# nixie-fader_rev3.net
KiCad netlist of a schematic drawn in EAGLE
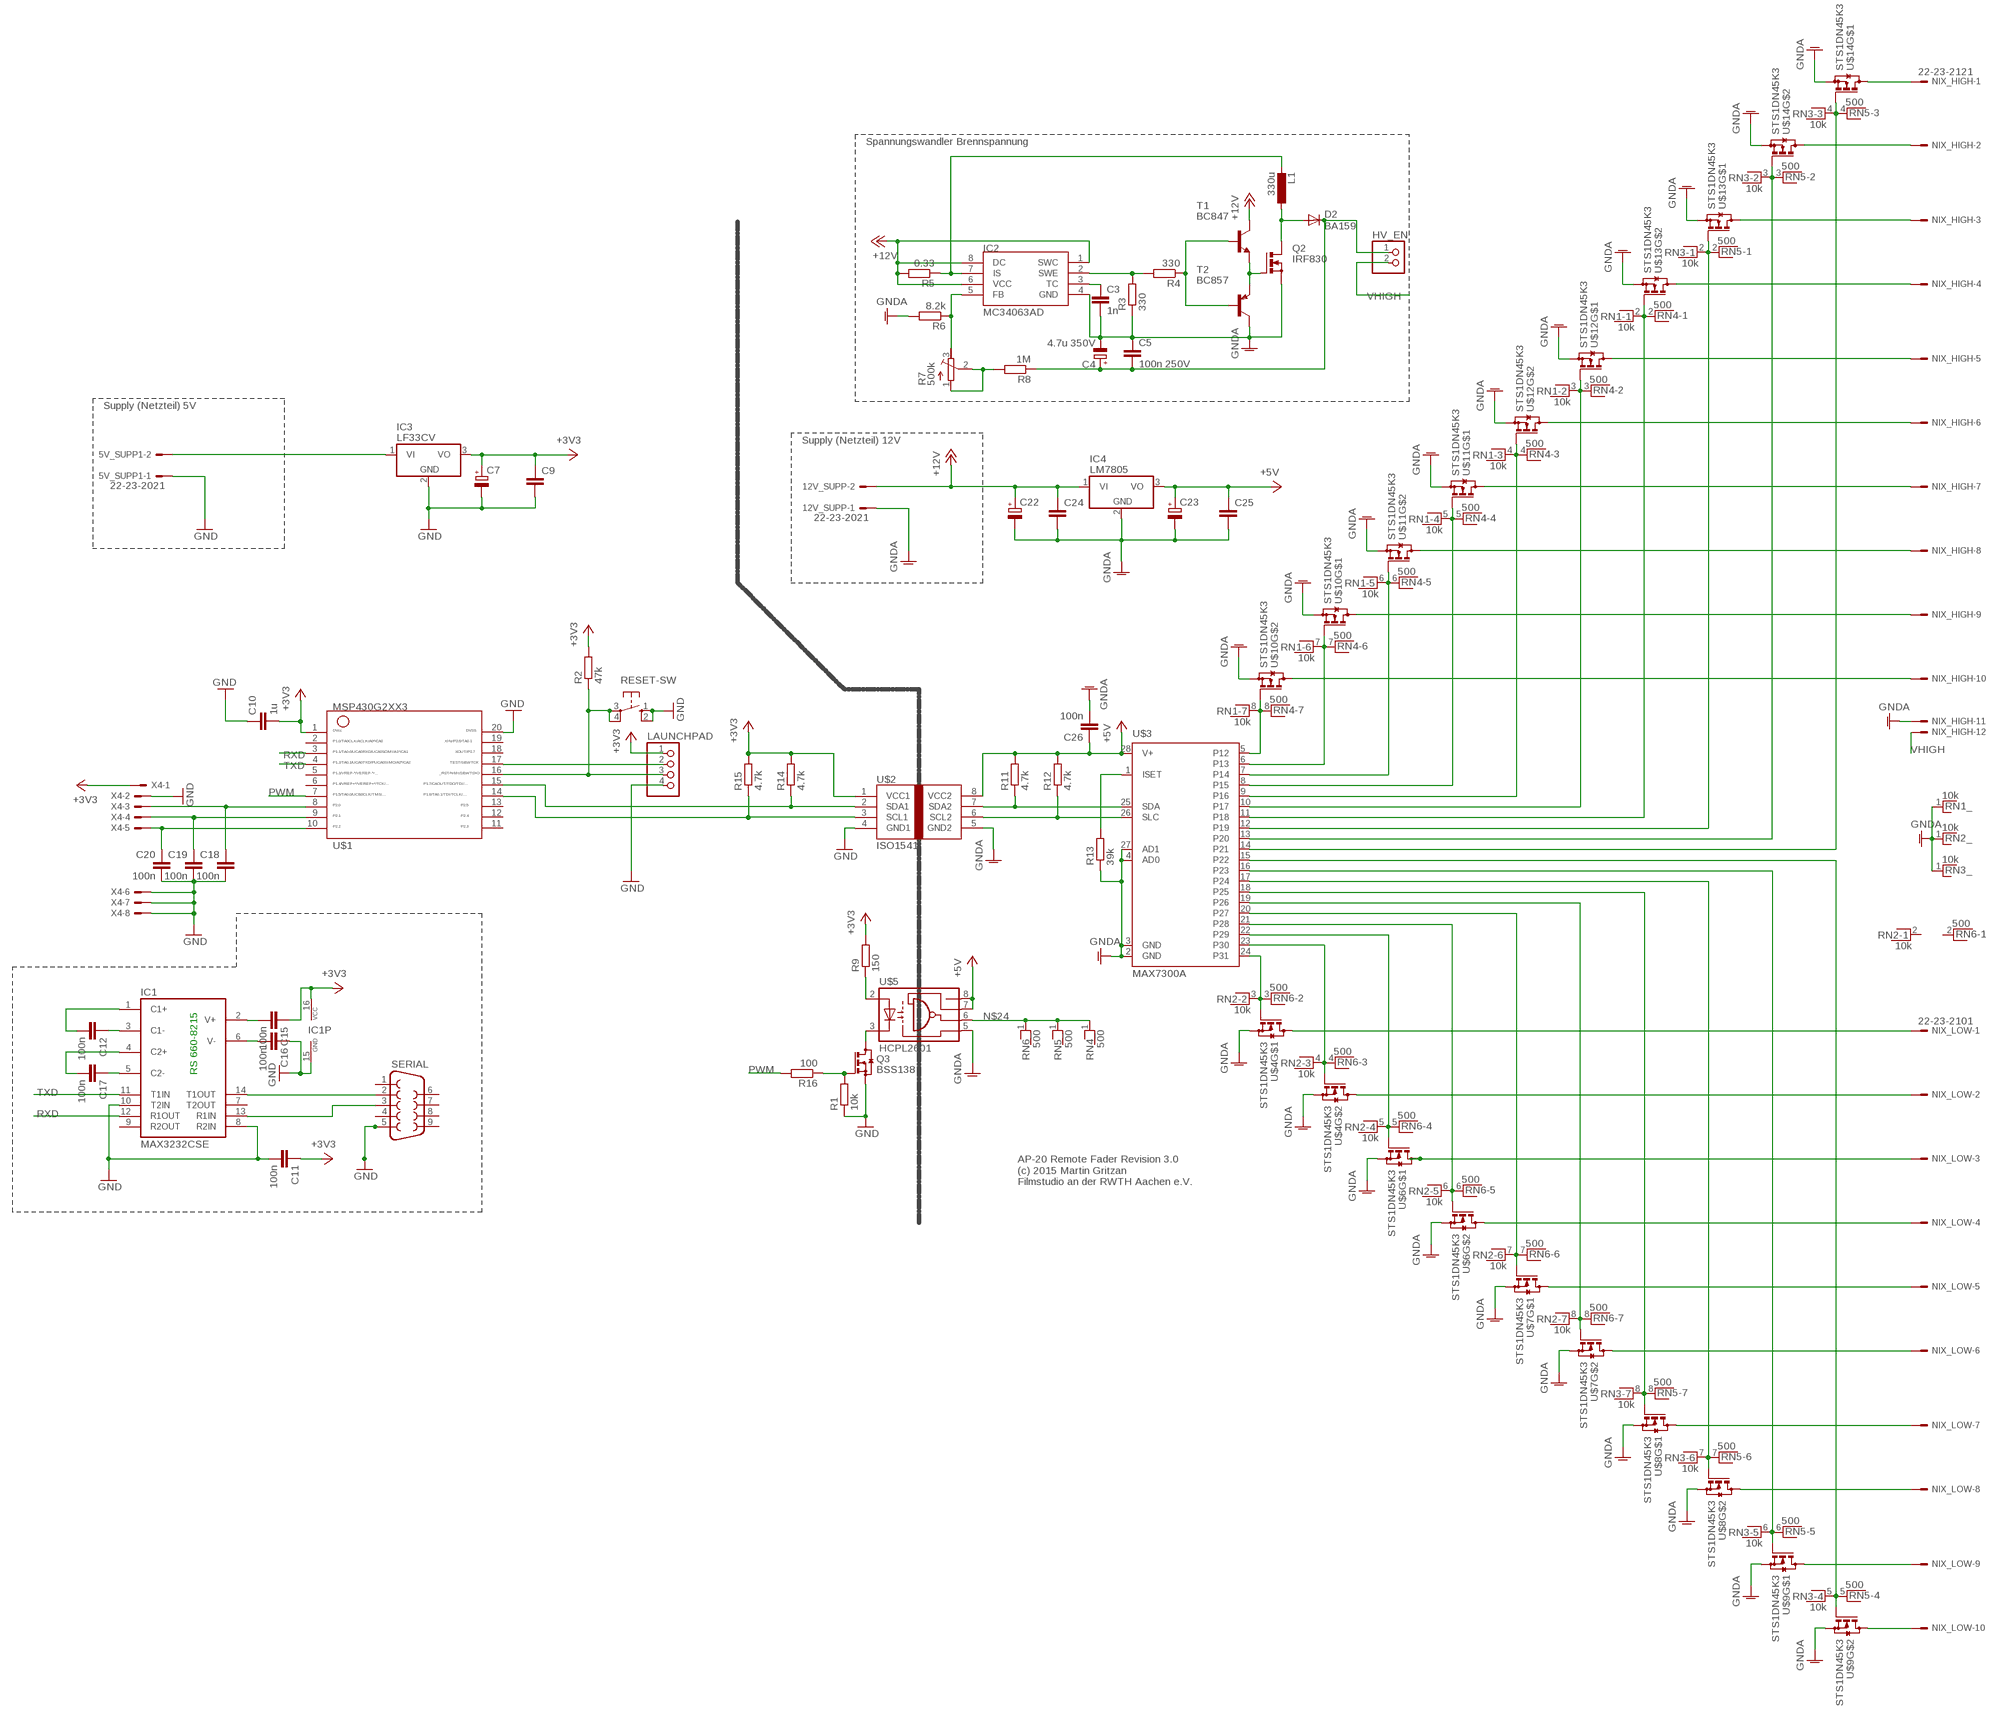
[diagram p0: schematic, sheet 1]

(export (version "E")
  (design (tool "Eeschema 10.0.6"))
  (components
    (comp (ref "5V_SUPP1")
      (value "22-23-2021")
      (footprint "eagle-import:22-23-2021")
      (fields (field (name "MF") "MOLEX"))
      (libsource (lib "eagle-import") (part "22-23-2021"))
    )
    (comp (ref "12V_SUPP")
      (value "22-23-2021")
      (footprint "eagle-import:22-23-2021")
      (fields (field (name "MF") "MOLEX"))
      (libsource (lib "eagle-import") (part "22-23-2021"))
    )
    (comp (ref "C3")
      (value "1n")
      (footprint "eagle-import:C0805")
      (libsource (lib "eagle-import") (part "resistor_C-EUC0805"))
    )
    (comp (ref "C4")
      (value "4.7u 350V")
      (footprint "eagle-import:E5-8,5")
      (libsource (lib "eagle-import") (part "resistor_CPOL-EUE5-8.5"))
    )
    (comp (ref "C5")
      (value "100n 250V")
      (footprint "eagle-import:C050-024X044")
      (libsource (lib "eagle-import") (part "C-EU050-024X044"))
    )
    (comp (ref "C7")
      (value "CPOL-EU140CLH-0810")
      (footprint "eagle-import:140CLH-0810")
      (libsource (lib "eagle-import") (part "CPOL-EU140CLH-0810"))
    )
    (comp (ref "C9")
      (value "C-EUC0805K")
      (footprint "eagle-import:C0805K")
      (libsource (lib "eagle-import") (part "C-EUC0805K"))
    )
    (comp (ref "C10")
      (value "1u")
      (footprint "eagle-import:C0805K")
      (libsource (lib "eagle-import") (part "C-EUC0805K"))
    )
    (comp (ref "C11")
      (value "100n")
      (footprint "eagle-import:C0805")
      (libsource (lib "eagle-import") (part "resistor_C-EUC0805"))
    )
    (comp (ref "C12")
      (value "100n")
      (footprint "eagle-import:C0805")
      (libsource (lib "eagle-import") (part "resistor_C-EUC0805"))
    )
    (comp (ref "C15")
      (value "100n")
      (footprint "eagle-import:C0805")
      (libsource (lib "eagle-import") (part "resistor_C-EUC0805"))
    )
    (comp (ref "C16")
      (value "100n")
      (footprint "eagle-import:C0805")
      (libsource (lib "eagle-import") (part "resistor_C-EUC0805"))
    )
    (comp (ref "C17")
      (value "100n")
      (footprint "eagle-import:C0805")
      (libsource (lib "eagle-import") (part "resistor_C-EUC0805"))
    )
    (comp (ref "C18")
      (value "100n")
      (footprint "eagle-import:C0805")
      (libsource (lib "eagle-import") (part "resistor_C-EUC0805"))
    )
    (comp (ref "C19")
      (value "100n")
      (footprint "eagle-import:C0805")
      (libsource (lib "eagle-import") (part "resistor_C-EUC0805"))
    )
    (comp (ref "C20")
      (value "100n")
      (footprint "eagle-import:C0805")
      (libsource (lib "eagle-import") (part "resistor_C-EUC0805"))
    )
    (comp (ref "C22")
      (value "CPOL-EU140CLH-0810")
      (footprint "eagle-import:140CLH-0810")
      (libsource (lib "eagle-import") (part "CPOL-EU140CLH-0810"))
    )
    (comp (ref "C23")
      (value "CPOL-EU140CLH-0810")
      (footprint "eagle-import:140CLH-0810")
      (libsource (lib "eagle-import") (part "CPOL-EU140CLH-0810"))
    )
    (comp (ref "C24")
      (value "C-EUC0805K")
      (footprint "eagle-import:C0805K")
      (libsource (lib "eagle-import") (part "C-EUC0805K"))
    )
    (comp (ref "C25")
      (value "C-EUC0805K")
      (footprint "eagle-import:C0805K")
      (libsource (lib "eagle-import") (part "C-EUC0805K"))
    )
    (comp (ref "C26")
      (value "100n")
      (footprint "eagle-import:C0805")
      (libsource (lib "eagle-import") (part "resistor_C-EUC0805"))
    )
    (comp (ref "D2")
      (value "BA159")
      (footprint "eagle-import:P1-10")
      (libsource (lib "eagle-import") (part "BA157"))
    )
    (comp (ref "HV_EN")
      (value "PINHD-1X2")
      (footprint "eagle-import:1X02")
      (libsource (lib "eagle-import") (part "PINHD-1X2"))
    )
    (comp (ref "IC1")
      (value "MAX3232CSE")
      (footprint "eagle-import:SO16")
      (libsource (lib "eagle-import") (part "MAX3232SEC"))
    )
    (comp (ref "IC2")
      (value "MC34063AD")
      (footprint "eagle-import:SOIC8")
      (libsource (lib "eagle-import") (part "MC34063AD"))
    )
    (comp (ref "IC3")
      (value "LF33CV")
      (footprint "eagle-import:TO220V")
      (libsource (lib "eagle-import") (part "78TV05"))
    )
    (comp (ref "IC4")
      (value "LM7805")
      (footprint "eagle-import:TO220V")
      (libsource (lib "eagle-import") (part "78TV05"))
    )
    (comp (ref "L1")
      (value "330u")
      (footprint "eagle-import:IRF36")
      (libsource (lib "eagle-import") (part "L-EUIRF-36"))
    )
    (comp (ref "LAUNCHPAD")
      (value "PINHD-1X4")
      (footprint "eagle-import:1X04")
      (libsource (lib "eagle-import") (part "PINHD-1X4"))
    )
    (comp (ref "NIX_HIGH")
      (value "22-23-2121")
      (footprint "eagle-import:22-23-2121")
      (fields (field (name "MF") "MOLEX"))
      (libsource (lib "eagle-import") (part "22-23-2121"))
    )
    (comp (ref "NIX_LOW")
      (value "22-23-2101")
      (footprint "eagle-import:22-23-2101")
      (fields (field (name "MF") "MOLEX"))
      (libsource (lib "eagle-import") (part "22-23-2101"))
    )
    (comp (ref "Q2")
      (value "IRF830")
      (footprint "eagle-import:TO220BV")
      (libsource (lib "eagle-import") (part "IRF512"))
    )
    (comp (ref "Q3")
      (value "BSS138")
      (footprint "eagle-import:SOT23")
      (libsource (lib "eagle-import") (part "BSS123"))
    )
    (comp (ref "R1")
      (value "10k")
      (footprint "eagle-import:M0805")
      (libsource (lib "eagle-import") (part "R-EU_M0805"))
    )
    (comp (ref "R2")
      (value "47k")
      (footprint "eagle-import:R0805")
      (libsource (lib "eagle-import") (part "R-EU_R0805"))
    )
    (comp (ref "R3")
      (value "330")
      (footprint "eagle-import:M0805")
      (libsource (lib "eagle-import") (part "R-EU_M0805"))
    )
    (comp (ref "R4")
      (value "330")
      (footprint "eagle-import:M0805")
      (libsource (lib "eagle-import") (part "R-EU_M0805"))
    )
    (comp (ref "R5")
      (value "0.33")
      (footprint "eagle-import:M0805")
      (libsource (lib "eagle-import") (part "R-EU_M0805"))
    )
    (comp (ref "R6")
      (value "8.2k")
      (footprint "eagle-import:M0805")
      (libsource (lib "eagle-import") (part "R-EU_M0805"))
    )
    (comp (ref "R7")
      (value "500k")
      (footprint "eagle-import:RTRIM3296Y")
      (libsource (lib "eagle-import") (part "R-TRIMM3296Y"))
    )
    (comp (ref "R8")
      (value "1M")
      (footprint "eagle-import:M0805")
      (libsource (lib "eagle-import") (part "R-EU_M0805"))
    )
    (comp (ref "R9")
      (value "150")
      (footprint "eagle-import:M0805")
      (libsource (lib "eagle-import") (part "R-EU_M0805"))
    )
    (comp (ref "R11")
      (value "4.7k")
      (footprint "eagle-import:M0805")
      (libsource (lib "eagle-import") (part "R-EU_M0805"))
    )
    (comp (ref "R12")
      (value "4.7k")
      (footprint "eagle-import:M0805")
      (libsource (lib "eagle-import") (part "R-EU_M0805"))
    )
    (comp (ref "R13")
      (value "39k")
      (footprint "eagle-import:M0805")
      (libsource (lib "eagle-import") (part "R-EU_M0805"))
    )
    (comp (ref "R14")
      (value "4.7k")
      (footprint "eagle-import:M0805")
      (libsource (lib "eagle-import") (part "R-EU_M0805"))
    )
    (comp (ref "R15")
      (value "4.7k")
      (footprint "eagle-import:M0805")
      (libsource (lib "eagle-import") (part "R-EU_M0805"))
    )
    (comp (ref "R16")
      (value "100")
      (footprint "eagle-import:M0805")
      (libsource (lib "eagle-import") (part "R-EU_M0805"))
    )
    (comp (ref "RESET-SW")
      (value "10-XX")
      (footprint "eagle-import:B3F-10XX")
      (fields (field (name "MPN") "B3F-1000"))
      (libsource (lib "eagle-import") (part "10-XX"))
    )
    (comp (ref "RN1")
      (value "10k")
      (footprint "eagle-import:RN-8")
      (libsource (lib "eagle-import") (part "RNX7"))
    )
    (comp (ref "RN2")
      (value "10k")
      (footprint "eagle-import:RN-8")
      (libsource (lib "eagle-import") (part "RNX7"))
    )
    (comp (ref "RN3")
      (value "10k")
      (footprint "eagle-import:RN-8")
      (libsource (lib "eagle-import") (part "RNX7"))
    )
    (comp (ref "RN4")
      (value "500")
      (footprint "eagle-import:RN-8")
      (libsource (lib "eagle-import") (part "RNX7"))
    )
    (comp (ref "RN5")
      (value "500")
      (footprint "eagle-import:RN-8")
      (libsource (lib "eagle-import") (part "RNX7"))
    )
    (comp (ref "RN6")
      (value "500")
      (footprint "eagle-import:RN-8")
      (libsource (lib "eagle-import") (part "RNX7"))
    )
    (comp (ref "SERIAL")
      (value "F09H")
      (footprint "eagle-import:F09H")
      (libsource (lib "eagle-import") (part "F09H"))
    )
    (comp (ref "T1")
      (value "BC847")
      (footprint "eagle-import:SOT23")
      (libsource (lib "eagle-import") (part "BC847"))
    )
    (comp (ref "T2")
      (value "BC857")
      (footprint "eagle-import:SOT23-BEC")
      (libsource (lib "eagle-import") (part "BC857SMDA"))
    )
    (comp (ref "U$1")
      (value "G2XX3---PW20")
      (footprint "eagle-import:PW20")
      (libsource (lib "eagle-import") (part "G2XX3---PW20"))
    )
    (comp (ref "U$2")
      (value "ISO1541")
      (footprint "eagle-import:SOIC8")
      (libsource (lib "eagle-import") (part "ISO1541"))
    )
    (comp (ref "U$3")
      (value "MAX7300A")
      (footprint "eagle-import:SSOP28")
      (libsource (lib "eagle-import") (part "MAX7300A"))
    )
    (comp (ref "U$4")
      (value "STS1DN45K3")
      (footprint "eagle-import:SO08")
      (libsource (lib "eagle-import") (part "STS1DN45K3"))
    )
    (comp (ref "U$5")
      (value "HCPL2601")
      (footprint "eagle-import:DIP8-SMD")
      (libsource (lib "eagle-import") (part "HCPL2601"))
    )
    (comp (ref "U$6")
      (value "STS1DN45K3")
      (footprint "eagle-import:SO08")
      (libsource (lib "eagle-import") (part "STS1DN45K3"))
    )
    (comp (ref "U$7")
      (value "STS1DN45K3")
      (footprint "eagle-import:SO08")
      (libsource (lib "eagle-import") (part "STS1DN45K3"))
    )
    (comp (ref "U$8")
      (value "STS1DN45K3")
      (footprint "eagle-import:SO08")
      (libsource (lib "eagle-import") (part "STS1DN45K3"))
    )
    (comp (ref "U$9")
      (value "STS1DN45K3")
      (footprint "eagle-import:SO08")
      (libsource (lib "eagle-import") (part "STS1DN45K3"))
    )
    (comp (ref "U$10")
      (value "STS1DN45K3")
      (footprint "eagle-import:SO08")
      (libsource (lib "eagle-import") (part "STS1DN45K3"))
    )
    (comp (ref "U$11")
      (value "STS1DN45K3")
      (footprint "eagle-import:SO08")
      (libsource (lib "eagle-import") (part "STS1DN45K3"))
    )
    (comp (ref "U$12")
      (value "STS1DN45K3")
      (footprint "eagle-import:SO08")
      (libsource (lib "eagle-import") (part "STS1DN45K3"))
    )
    (comp (ref "U$13")
      (value "STS1DN45K3")
      (footprint "eagle-import:SO08")
      (libsource (lib "eagle-import") (part "STS1DN45K3"))
    )
    (comp (ref "U$14")
      (value "STS1DN45K3")
      (footprint "eagle-import:SO08")
      (libsource (lib "eagle-import") (part "STS1DN45K3"))
    )
    (comp (ref "X4")
      (value "22-23-2081")
      (footprint "eagle-import:22-23-2081")
      (fields (field (name "MF") "MOLEX"))
      (libsource (lib "eagle-import") (part "22-23-2081"))
    )
  )
  (nets
    (net (code "1") (name "+3V3") (class "Default")
      (node (ref "C10") (pin "2") (pinfunction "2_2") (pintype "passive"))
      (node (ref "C11") (pin "1") (pinfunction "1_1") (pintype "passive"))
      (node (ref "C15") (pin "1") (pinfunction "1_1") (pintype "passive"))
      (node (ref "C7") (pin "+") (pinfunction "+_+") (pintype "passive"))
      (node (ref "C9") (pin "1") (pinfunction "1_1") (pintype "passive"))
      (node (ref "IC1") (pin "16") (pinfunction "VCC_16") (pintype "power_in"))
      (node (ref "IC3") (pin "3") (pinfunction "VO_3") (pintype "passive"))
      (node (ref "LAUNCHPAD") (pin "1") (pinfunction "1_1") (pintype "passive"))
      (node (ref "R14") (pin "2") (pinfunction "2_2") (pintype "passive"))
      (node (ref "R15") (pin "2") (pinfunction "2_2") (pintype "passive"))
      (node (ref "R2") (pin "2") (pinfunction "2_2") (pintype "passive"))
      (node (ref "R9") (pin "2") (pinfunction "2_2") (pintype "passive"))
      (node (ref "U$1") (pin "1") (pinfunction "1_1") (pintype "bidirectional"))
      (node (ref "U$2") (pin "1") (pinfunction "VCC1_1") (pintype "power_in"))
      (node (ref "X4") (pin "1") (pinfunction "S_1") (pintype "passive"))
    )
    (net (code "2") (name "+5V") (class "Default")
      (node (ref "C23") (pin "+") (pinfunction "+_+") (pintype "passive"))
      (node (ref "C25") (pin "1") (pinfunction "1_1") (pintype "passive"))
      (node (ref "C26") (pin "1") (pinfunction "1_1") (pintype "passive"))
      (node (ref "IC4") (pin "3") (pinfunction "VO_3") (pintype "passive"))
      (node (ref "R11") (pin "2") (pinfunction "2_2") (pintype "passive"))
      (node (ref "R12") (pin "2") (pinfunction "2_2") (pintype "passive"))
      (node (ref "U$2") (pin "8") (pinfunction "VCC2_8") (pintype "power_in"))
      (node (ref "U$3") (pin "28") (pinfunction "V+_28") (pintype "power_in"))
      (node (ref "U$5") (pin "7") (pinfunction "EN_7") (pintype "passive"))
      (node (ref "U$5") (pin "8") (pinfunction "VCC_8") (pintype "passive"))
    )
    (net (code "3") (name "+12V") (class "Default")
      (node (ref "12V_SUPP") (pin "2") (pinfunction "S_2") (pintype "passive"))
      (node (ref "C22") (pin "+") (pinfunction "+_+") (pintype "passive"))
      (node (ref "C24") (pin "1") (pinfunction "1_1") (pintype "passive"))
      (node (ref "IC2") (pin "1") (pinfunction "SWC_1") (pintype "passive"))
      (node (ref "IC2") (pin "6") (pinfunction "VCC_6") (pintype "passive"))
      (node (ref "IC2") (pin "8") (pinfunction "DC_8") (pintype "passive"))
      (node (ref "IC4") (pin "1") (pinfunction "VI_1") (pintype "input"))
      (node (ref "R5") (pin "2") (pinfunction "2_2") (pintype "passive"))
      (node (ref "T1") (pin "3") (pinfunction "C_3") (pintype "passive"))
    )
    (net (code "4") (name "/N$24") (class "Default")
      (node (ref "RN4") (pin "1") (pinfunction "1_1") (pintype "passive"))
      (node (ref "RN5") (pin "1") (pinfunction "1_1") (pintype "passive"))
      (node (ref "RN6") (pin "1") (pinfunction "1_1") (pintype "passive"))
      (node (ref "U$5") (pin "6") (pinfunction "OUT_6") (pintype "passive"))
    )
    (net (code "5") (name "/PWM") (class "Default")
      (node (ref "R16") (pin "2") (pinfunction "2_2") (pintype "passive"))
      (node (ref "U$1") (pin "7") (pinfunction "7_7") (pintype "bidirectional"))
    )
    (net (code "6") (name "/RXD") (class "Default")
      (node (ref "IC1") (pin "12") (pinfunction "R1OUT_12") (pintype "output"))
      (node (ref "U$1") (pin "3") (pinfunction "3_3") (pintype "bidirectional"))
    )
    (net (code "7") (name "/TXD") (class "Default")
      (node (ref "IC1") (pin "11") (pinfunction "T1IN_11") (pintype "input"))
      (node (ref "U$1") (pin "4") (pinfunction "4_4") (pintype "bidirectional"))
    )
    (net (code "8") (name "/VHIGH") (class "Default")
      (node (ref "HV_EN") (pin "2") (pinfunction "2_2") (pintype "passive"))
      (node (ref "NIX_HIGH") (pin "12") (pinfunction "S_12") (pintype "passive"))
    )
    (net (code "9") (name "GND") (class "Default")
      (node (ref "5V_SUPP1") (pin "1") (pinfunction "S_1") (pintype "passive"))
      (node (ref "C10") (pin "1") (pinfunction "1_1") (pintype "passive"))
      (node (ref "C11") (pin "2") (pinfunction "2_2") (pintype "passive"))
      (node (ref "C16") (pin "1") (pinfunction "1_1") (pintype "passive"))
      (node (ref "C18") (pin "2") (pinfunction "2_2") (pintype "passive"))
      (node (ref "C19") (pin "2") (pinfunction "2_2") (pintype "passive"))
      (node (ref "C20") (pin "2") (pinfunction "2_2") (pintype "passive"))
      (node (ref "C7") (pin "-") (pinfunction "-_-") (pintype "passive"))
      (node (ref "C9") (pin "2") (pinfunction "2_2") (pintype "passive"))
      (node (ref "IC1") (pin "10") (pinfunction "T2IN_10") (pintype "input"))
      (node (ref "IC1") (pin "15") (pinfunction "GND_15") (pintype "power_in"))
      (node (ref "IC1") (pin "8") (pinfunction "R2IN_8") (pintype "input"))
      (node (ref "IC3") (pin "2") (pinfunction "GND_2") (pintype "passive"))
      (node (ref "LAUNCHPAD") (pin "4") (pinfunction "4_4") (pintype "passive"))
      (node (ref "Q3") (pin "2") (pinfunction "S_2") (pintype "passive"))
      (node (ref "R1") (pin "1") (pinfunction "1_1") (pintype "passive"))
      (node (ref "RESET-SW") (pin "1") (pinfunction "S_1") (pintype "passive"))
      (node (ref "RESET-SW") (pin "2") (pinfunction "S1_2") (pintype "passive"))
      (node (ref "SERIAL") (pin "5") (pinfunction "5_5") (pintype "passive"))
      (node (ref "U$1") (pin "20") (pinfunction "20_20") (pintype "bidirectional"))
      (node (ref "U$2") (pin "4") (pinfunction "GND1_4") (pintype "power_in"))
      (node (ref "X4") (pin "2") (pinfunction "S_2") (pintype "passive"))
      (node (ref "X4") (pin "6") (pinfunction "S_6") (pintype "passive"))
      (node (ref "X4") (pin "7") (pinfunction "S_7") (pintype "passive"))
      (node (ref "X4") (pin "8") (pinfunction "S_8") (pintype "passive"))
    )
    (net (code "10") (name "GNDA") (class "Default")
      (node (ref "12V_SUPP") (pin "1") (pinfunction "S_1") (pintype "passive"))
      (node (ref "C22") (pin "-") (pinfunction "-_-") (pintype "passive"))
      (node (ref "C23") (pin "-") (pinfunction "-_-") (pintype "passive"))
      (node (ref "C24") (pin "2") (pinfunction "2_2") (pintype "passive"))
      (node (ref "C25") (pin "2") (pinfunction "2_2") (pintype "passive"))
      (node (ref "C26") (pin "2") (pinfunction "2_2") (pintype "passive"))
      (node (ref "C3") (pin "2") (pinfunction "2_2") (pintype "passive"))
      (node (ref "C4") (pin "-") (pinfunction "-_-") (pintype "passive"))
      (node (ref "C5") (pin "1") (pinfunction "1_1") (pintype "passive"))
      (node (ref "IC2") (pin "4") (pinfunction "GND_4") (pintype "passive"))
      (node (ref "IC4") (pin "2") (pinfunction "GND_2") (pintype "passive"))
      (node (ref "NIX_HIGH") (pin "11") (pinfunction "S_11") (pintype "passive"))
      (node (ref "Q2") (pin "S") (pinfunction "S_S") (pintype "passive"))
      (node (ref "R13") (pin "1") (pinfunction "1_1") (pintype "passive"))
      (node (ref "R3") (pin "1") (pinfunction "1_1") (pintype "passive"))
      (node (ref "R6") (pin "2") (pinfunction "2_2") (pintype "passive"))
      (node (ref "RN1") (pin "1") (pinfunction "1_1") (pintype "passive"))
      (node (ref "RN2") (pin "1") (pinfunction "1_1") (pintype "passive"))
      (node (ref "RN3") (pin "1") (pinfunction "1_1") (pintype "passive"))
      (node (ref "T2") (pin "C") (pinfunction "C_C") (pintype "passive"))
      (node (ref "U$10") (pin "1") (pinfunction "S_1") (pintype "passive"))
      (node (ref "U$10") (pin "3") (pinfunction "S_3") (pintype "passive"))
      (node (ref "U$11") (pin "1") (pinfunction "S_1") (pintype "passive"))
      (node (ref "U$11") (pin "3") (pinfunction "S_3") (pintype "passive"))
      (node (ref "U$12") (pin "1") (pinfunction "S_1") (pintype "passive"))
      (node (ref "U$12") (pin "3") (pinfunction "S_3") (pintype "passive"))
      (node (ref "U$13") (pin "1") (pinfunction "S_1") (pintype "passive"))
      (node (ref "U$13") (pin "3") (pinfunction "S_3") (pintype "passive"))
      (node (ref "U$14") (pin "1") (pinfunction "S_1") (pintype "passive"))
      (node (ref "U$14") (pin "3") (pinfunction "S_3") (pintype "passive"))
      (node (ref "U$2") (pin "5") (pinfunction "GND2_5") (pintype "power_in"))
      (node (ref "U$3") (pin "2") (pinfunction "GND_2") (pintype "power_in"))
      (node (ref "U$3") (pin "27") (pinfunction "AD1_27") (pintype "input"))
      (node (ref "U$3") (pin "3") (pinfunction "GND_3") (pintype "power_in"))
      (node (ref "U$3") (pin "4") (pinfunction "AD0_4") (pintype "input"))
      (node (ref "U$4") (pin "1") (pinfunction "S_1") (pintype "passive"))
      (node (ref "U$4") (pin "3") (pinfunction "S_3") (pintype "passive"))
      (node (ref "U$5") (pin "5") (pinfunction "GND_5") (pintype "passive"))
      (node (ref "U$6") (pin "1") (pinfunction "S_1") (pintype "passive"))
      (node (ref "U$6") (pin "3") (pinfunction "S_3") (pintype "passive"))
      (node (ref "U$7") (pin "1") (pinfunction "S_1") (pintype "passive"))
      (node (ref "U$7") (pin "3") (pinfunction "S_3") (pintype "passive"))
      (node (ref "U$8") (pin "1") (pinfunction "S_1") (pintype "passive"))
      (node (ref "U$8") (pin "3") (pinfunction "S_3") (pintype "passive"))
      (node (ref "U$9") (pin "1") (pinfunction "S_1") (pintype "passive"))
      (node (ref "U$9") (pin "3") (pinfunction "S_3") (pintype "passive"))
    )
    (net (code "11") (name "Net-(5V_SUPP1B-S)") (class "Default")
      (node (ref "5V_SUPP1") (pin "2") (pinfunction "S_2") (pintype "passive"))
      (node (ref "IC3") (pin "1") (pinfunction "VI_1") (pintype "input"))
    )
    (net (code "12") (name "Net-(C4-Pad+)") (class "Default")
      (node (ref "C4") (pin "+") (pinfunction "+_+") (pintype "passive"))
      (node (ref "C5") (pin "2") (pinfunction "2_2") (pintype "passive"))
      (node (ref "D2") (pin "C") (pinfunction "C_C") (pintype "passive"))
      (node (ref "HV_EN") (pin "1") (pinfunction "1_1") (pintype "passive"))
      (node (ref "R8") (pin "1") (pinfunction "1_1") (pintype "passive"))
    )
    (net (code "13") (name "Net-(D2-PadA)") (class "Default")
      (node (ref "D2") (pin "A") (pinfunction "A_A") (pintype "passive"))
      (node (ref "L1") (pin "1") (pinfunction "1_1") (pintype "passive"))
      (node (ref "Q2") (pin "D") (pinfunction "D_D") (pintype "passive"))
    )
    (net (code "14") (name "Net-(IC1A-C1+)") (class "Default")
      (node (ref "C12") (pin "2") (pinfunction "2_2") (pintype "passive"))
      (node (ref "IC1") (pin "1") (pinfunction "C1+_1") (pintype "bidirectional"))
    )
    (net (code "15") (name "Net-(IC1A-C1-)") (class "Default")
      (node (ref "C12") (pin "1") (pinfunction "1_1") (pintype "passive"))
      (node (ref "IC1") (pin "3") (pinfunction "C1-_3") (pintype "bidirectional"))
    )
    (net (code "16") (name "Net-(IC1A-C2+)") (class "Default")
      (node (ref "C17") (pin "2") (pinfunction "2_2") (pintype "passive"))
      (node (ref "IC1") (pin "4") (pinfunction "C2+_4") (pintype "bidirectional"))
    )
    (net (code "17") (name "Net-(IC1A-C2-)") (class "Default")
      (node (ref "C17") (pin "1") (pinfunction "1_1") (pintype "passive"))
      (node (ref "IC1") (pin "5") (pinfunction "C2-_5") (pintype "bidirectional"))
    )
    (net (code "18") (name "Net-(IC1A-R1IN)") (class "Default")
      (node (ref "IC1") (pin "13") (pinfunction "R1IN_13") (pintype "input"))
      (node (ref "SERIAL") (pin "3") (pinfunction "3_3") (pintype "passive"))
    )
    (net (code "19") (name "Net-(IC1A-T1OUT)") (class "Default")
      (node (ref "IC1") (pin "14") (pinfunction "T1OUT_14") (pintype "output"))
      (node (ref "SERIAL") (pin "2") (pinfunction "2_2") (pintype "passive"))
    )
    (net (code "20") (name "Net-(IC1A-V+)") (class "Default")
      (node (ref "C15") (pin "2") (pinfunction "2_2") (pintype "passive"))
      (node (ref "IC1") (pin "2") (pinfunction "V+_2") (pintype "bidirectional"))
    )
    (net (code "21") (name "Net-(IC1A-V-)") (class "Default")
      (node (ref "C16") (pin "2") (pinfunction "2_2") (pintype "passive"))
      (node (ref "IC1") (pin "6") (pinfunction "V-_6") (pintype "bidirectional"))
    )
    (net (code "22") (name "Net-(IC2-FB)") (class "Default")
      (node (ref "IC2") (pin "5") (pinfunction "FB_5") (pintype "passive"))
      (node (ref "R6") (pin "1") (pinfunction "1_1") (pintype "passive"))
      (node (ref "R7") (pin "3") (pinfunction "A_3") (pintype "passive"))
    )
    (net (code "23") (name "Net-(IC2-IS)") (class "Default")
      (node (ref "IC2") (pin "7") (pinfunction "IS_7") (pintype "passive"))
      (node (ref "L1") (pin "2") (pinfunction "2_2") (pintype "passive"))
      (node (ref "R5") (pin "1") (pinfunction "1_1") (pintype "passive"))
    )
    (net (code "24") (name "Net-(IC2-SWE)") (class "Default")
      (node (ref "IC2") (pin "2") (pinfunction "SWE_2") (pintype "passive"))
      (node (ref "R3") (pin "2") (pinfunction "2_2") (pintype "passive"))
      (node (ref "R4") (pin "2") (pinfunction "2_2") (pintype "passive"))
    )
    (net (code "25") (name "Net-(IC2-TC)") (class "Default")
      (node (ref "C3") (pin "1") (pinfunction "1_1") (pintype "passive"))
      (node (ref "IC2") (pin "3") (pinfunction "TC_3") (pintype "passive"))
    )
    (net (code "26") (name "Net-(LAUNCHPAD-Pad2)") (class "Default")
      (node (ref "LAUNCHPAD") (pin "2") (pinfunction "2_2") (pintype "passive"))
      (node (ref "U$1") (pin "17") (pinfunction "17_17") (pintype "bidirectional"))
    )
    (net (code "27") (name "Net-(NIX_HIGHA-S)") (class "Default")
      (node (ref "NIX_HIGH") (pin "1") (pinfunction "S_1") (pintype "passive"))
      (node (ref "U$14") (pin "7") (pinfunction "D_7") (pintype "passive"))
      (node (ref "U$14") (pin "8") (pinfunction "D_8") (pintype "passive"))
    )
    (net (code "28") (name "Net-(NIX_HIGHB-S)") (class "Default")
      (node (ref "NIX_HIGH") (pin "10") (pinfunction "S_10") (pintype "passive"))
      (node (ref "U$10") (pin "5") (pinfunction "D_5") (pintype "passive"))
      (node (ref "U$10") (pin "6") (pinfunction "D_6") (pintype "passive"))
    )
    (net (code "29") (name "Net-(NIX_HIGHE-S)") (class "Default")
      (node (ref "NIX_HIGH") (pin "2") (pinfunction "S_2") (pintype "passive"))
      (node (ref "U$14") (pin "5") (pinfunction "D_5") (pintype "passive"))
      (node (ref "U$14") (pin "6") (pinfunction "D_6") (pintype "passive"))
    )
    (net (code "30") (name "Net-(NIX_HIGHF-S)") (class "Default")
      (node (ref "NIX_HIGH") (pin "3") (pinfunction "S_3") (pintype "passive"))
      (node (ref "U$13") (pin "7") (pinfunction "D_7") (pintype "passive"))
      (node (ref "U$13") (pin "8") (pinfunction "D_8") (pintype "passive"))
    )
    (net (code "31") (name "Net-(NIX_HIGHG-S)") (class "Default")
      (node (ref "NIX_HIGH") (pin "4") (pinfunction "S_4") (pintype "passive"))
      (node (ref "U$13") (pin "5") (pinfunction "D_5") (pintype "passive"))
      (node (ref "U$13") (pin "6") (pinfunction "D_6") (pintype "passive"))
    )
    (net (code "32") (name "Net-(NIX_HIGHH-S)") (class "Default")
      (node (ref "NIX_HIGH") (pin "5") (pinfunction "S_5") (pintype "passive"))
      (node (ref "U$12") (pin "7") (pinfunction "D_7") (pintype "passive"))
      (node (ref "U$12") (pin "8") (pinfunction "D_8") (pintype "passive"))
    )
    (net (code "33") (name "Net-(NIX_HIGHI-S)") (class "Default")
      (node (ref "NIX_HIGH") (pin "6") (pinfunction "S_6") (pintype "passive"))
      (node (ref "U$12") (pin "5") (pinfunction "D_5") (pintype "passive"))
      (node (ref "U$12") (pin "6") (pinfunction "D_6") (pintype "passive"))
    )
    (net (code "34") (name "Net-(NIX_HIGHJ-S)") (class "Default")
      (node (ref "NIX_HIGH") (pin "7") (pinfunction "S_7") (pintype "passive"))
      (node (ref "U$11") (pin "7") (pinfunction "D_7") (pintype "passive"))
      (node (ref "U$11") (pin "8") (pinfunction "D_8") (pintype "passive"))
    )
    (net (code "35") (name "Net-(NIX_HIGHK-S)") (class "Default")
      (node (ref "NIX_HIGH") (pin "8") (pinfunction "S_8") (pintype "passive"))
      (node (ref "U$11") (pin "5") (pinfunction "D_5") (pintype "passive"))
      (node (ref "U$11") (pin "6") (pinfunction "D_6") (pintype "passive"))
    )
    (net (code "36") (name "Net-(NIX_HIGHL-S)") (class "Default")
      (node (ref "NIX_HIGH") (pin "9") (pinfunction "S_9") (pintype "passive"))
      (node (ref "U$10") (pin "7") (pinfunction "D_7") (pintype "passive"))
      (node (ref "U$10") (pin "8") (pinfunction "D_8") (pintype "passive"))
    )
    (net (code "37") (name "Net-(NIX_LOWA-S)") (class "Default")
      (node (ref "NIX_LOW") (pin "1") (pinfunction "S_1") (pintype "passive"))
      (node (ref "U$4") (pin "7") (pinfunction "D_7") (pintype "passive"))
      (node (ref "U$4") (pin "8") (pinfunction "D_8") (pintype "passive"))
    )
    (net (code "38") (name "Net-(NIX_LOWB-S)") (class "Default")
      (node (ref "NIX_LOW") (pin "10") (pinfunction "S_10") (pintype "passive"))
      (node (ref "U$9") (pin "5") (pinfunction "D_5") (pintype "passive"))
      (node (ref "U$9") (pin "6") (pinfunction "D_6") (pintype "passive"))
    )
    (net (code "39") (name "Net-(NIX_LOWC-S)") (class "Default")
      (node (ref "NIX_LOW") (pin "2") (pinfunction "S_2") (pintype "passive"))
      (node (ref "U$4") (pin "5") (pinfunction "D_5") (pintype "passive"))
      (node (ref "U$4") (pin "6") (pinfunction "D_6") (pintype "passive"))
    )
    (net (code "40") (name "Net-(NIX_LOWD-S)") (class "Default")
      (node (ref "NIX_LOW") (pin "3") (pinfunction "S_3") (pintype "passive"))
      (node (ref "U$6") (pin "7") (pinfunction "D_7") (pintype "passive"))
      (node (ref "U$6") (pin "8") (pinfunction "D_8") (pintype "passive"))
    )
    (net (code "41") (name "Net-(NIX_LOWE-S)") (class "Default")
      (node (ref "NIX_LOW") (pin "4") (pinfunction "S_4") (pintype "passive"))
      (node (ref "U$6") (pin "5") (pinfunction "D_5") (pintype "passive"))
      (node (ref "U$6") (pin "6") (pinfunction "D_6") (pintype "passive"))
    )
    (net (code "42") (name "Net-(NIX_LOWF-S)") (class "Default")
      (node (ref "NIX_LOW") (pin "5") (pinfunction "S_5") (pintype "passive"))
      (node (ref "U$7") (pin "7") (pinfunction "D_7") (pintype "passive"))
      (node (ref "U$7") (pin "8") (pinfunction "D_8") (pintype "passive"))
    )
    (net (code "43") (name "Net-(NIX_LOWG-S)") (class "Default")
      (node (ref "NIX_LOW") (pin "6") (pinfunction "S_6") (pintype "passive"))
      (node (ref "U$7") (pin "5") (pinfunction "D_5") (pintype "passive"))
      (node (ref "U$7") (pin "6") (pinfunction "D_6") (pintype "passive"))
    )
    (net (code "44") (name "Net-(NIX_LOWH-S)") (class "Default")
      (node (ref "NIX_LOW") (pin "7") (pinfunction "S_7") (pintype "passive"))
      (node (ref "U$8") (pin "7") (pinfunction "D_7") (pintype "passive"))
      (node (ref "U$8") (pin "8") (pinfunction "D_8") (pintype "passive"))
    )
    (net (code "45") (name "Net-(NIX_LOWI-S)") (class "Default")
      (node (ref "NIX_LOW") (pin "8") (pinfunction "S_8") (pintype "passive"))
      (node (ref "U$8") (pin "5") (pinfunction "D_5") (pintype "passive"))
      (node (ref "U$8") (pin "6") (pinfunction "D_6") (pintype "passive"))
    )
    (net (code "46") (name "Net-(NIX_LOWJ-S)") (class "Default")
      (node (ref "NIX_LOW") (pin "9") (pinfunction "S_9") (pintype "passive"))
      (node (ref "U$9") (pin "7") (pinfunction "D_7") (pintype "passive"))
      (node (ref "U$9") (pin "8") (pinfunction "D_8") (pintype "passive"))
    )
    (net (code "47") (name "Net-(Q3-D)") (class "Default")
      (node (ref "Q3") (pin "3") (pinfunction "D_3") (pintype "passive"))
      (node (ref "U$5") (pin "3") (pinfunction "C_3") (pintype "passive"))
    )
    (net (code "48") (name "Net-(Q3-G)") (class "Default")
      (node (ref "Q3") (pin "1") (pinfunction "G_1") (pintype "passive"))
      (node (ref "R1") (pin "2") (pinfunction "2_2") (pintype "passive"))
      (node (ref "R16") (pin "1") (pinfunction "1_1") (pintype "passive"))
    )
    (net (code "49") (name "Net-(R7-E)") (class "Default")
      (node (ref "R7") (pin "1") (pinfunction "E_1") (pintype "passive"))
      (node (ref "R7") (pin "2") (pinfunction "S_2") (pintype "passive"))
      (node (ref "R8") (pin "2") (pinfunction "2_2") (pintype "passive"))
    )
    (net (code "50") (name "Net-(RESET-SW-P)") (class "Default")
      (node (ref "LAUNCHPAD") (pin "3") (pinfunction "3_3") (pintype "passive"))
      (node (ref "R2") (pin "1") (pinfunction "1_1") (pintype "passive"))
      (node (ref "RESET-SW") (pin "3") (pinfunction "P_3") (pintype "passive"))
      (node (ref "RESET-SW") (pin "4") (pinfunction "P1_4") (pintype "passive"))
      (node (ref "U$1") (pin "16") (pinfunction "16_16") (pintype "bidirectional"))
    )
    (net (code "51") (name "Net-(RN1A-1)") (class "Default")
      (node (ref "RN1") (pin "2") (pinfunction "1_2") (pintype "passive"))
      (node (ref "RN4") (pin "2") (pinfunction "1_2") (pintype "passive"))
      (node (ref "U$13") (pin "4") (pinfunction "G_4") (pintype "passive"))
      (node (ref "U$3") (pin "11") (pinfunction "P18_11") (pintype "bidirectional"))
    )
    (net (code "52") (name "Net-(RN1B-1)") (class "Default")
      (node (ref "RN1") (pin "3") (pinfunction "1_3") (pintype "passive"))
      (node (ref "RN4") (pin "3") (pinfunction "1_3") (pintype "passive"))
      (node (ref "U$12") (pin "2") (pinfunction "G_2") (pintype "passive"))
      (node (ref "U$3") (pin "10") (pinfunction "P17_10") (pintype "bidirectional"))
    )
    (net (code "53") (name "Net-(RN1C-1)") (class "Default")
      (node (ref "RN1") (pin "4") (pinfunction "1_4") (pintype "passive"))
      (node (ref "RN4") (pin "4") (pinfunction "1_4") (pintype "passive"))
      (node (ref "U$12") (pin "4") (pinfunction "G_4") (pintype "passive"))
      (node (ref "U$3") (pin "9") (pinfunction "P16_9") (pintype "bidirectional"))
    )
    (net (code "54") (name "Net-(RN1D-1)") (class "Default")
      (node (ref "RN1") (pin "5") (pinfunction "1_5") (pintype "passive"))
      (node (ref "RN4") (pin "5") (pinfunction "1_5") (pintype "passive"))
      (node (ref "U$11") (pin "2") (pinfunction "G_2") (pintype "passive"))
      (node (ref "U$3") (pin "8") (pinfunction "P15_8") (pintype "bidirectional"))
    )
    (net (code "55") (name "Net-(RN1E-1)") (class "Default")
      (node (ref "RN1") (pin "6") (pinfunction "1_6") (pintype "passive"))
      (node (ref "RN4") (pin "6") (pinfunction "1_6") (pintype "passive"))
      (node (ref "U$11") (pin "4") (pinfunction "G_4") (pintype "passive"))
      (node (ref "U$3") (pin "7") (pinfunction "P14_7") (pintype "bidirectional"))
    )
    (net (code "56") (name "Net-(RN1F-1)") (class "Default")
      (node (ref "RN1") (pin "7") (pinfunction "1_7") (pintype "passive"))
      (node (ref "RN4") (pin "7") (pinfunction "1_7") (pintype "passive"))
      (node (ref "U$10") (pin "2") (pinfunction "G_2") (pintype "passive"))
      (node (ref "U$3") (pin "6") (pinfunction "P13_6") (pintype "bidirectional"))
    )
    (net (code "57") (name "Net-(RN1G-1)") (class "Default")
      (node (ref "RN1") (pin "8") (pinfunction "1_8") (pintype "passive"))
      (node (ref "RN4") (pin "8") (pinfunction "1_8") (pintype "passive"))
      (node (ref "U$10") (pin "4") (pinfunction "G_4") (pintype "passive"))
      (node (ref "U$3") (pin "5") (pinfunction "P12_5") (pintype "bidirectional"))
    )
    (net (code "58") (name "Net-(RN2B-1)") (class "Default")
      (node (ref "RN2") (pin "3") (pinfunction "1_3") (pintype "passive"))
      (node (ref "RN6") (pin "3") (pinfunction "1_3") (pintype "passive"))
      (node (ref "U$3") (pin "24") (pinfunction "P31_24") (pintype "bidirectional"))
      (node (ref "U$4") (pin "2") (pinfunction "G_2") (pintype "passive"))
    )
    (net (code "59") (name "Net-(RN2C-1)") (class "Default")
      (node (ref "RN2") (pin "4") (pinfunction "1_4") (pintype "passive"))
      (node (ref "RN6") (pin "4") (pinfunction "1_4") (pintype "passive"))
      (node (ref "U$3") (pin "23") (pinfunction "P30_23") (pintype "bidirectional"))
      (node (ref "U$4") (pin "4") (pinfunction "G_4") (pintype "passive"))
    )
    (net (code "60") (name "Net-(RN2D-1)") (class "Default")
      (node (ref "RN2") (pin "5") (pinfunction "1_5") (pintype "passive"))
      (node (ref "RN6") (pin "5") (pinfunction "1_5") (pintype "passive"))
      (node (ref "U$3") (pin "22") (pinfunction "P29_22") (pintype "bidirectional"))
      (node (ref "U$6") (pin "2") (pinfunction "G_2") (pintype "passive"))
    )
    (net (code "61") (name "Net-(RN2E-1)") (class "Default")
      (node (ref "RN2") (pin "6") (pinfunction "1_6") (pintype "passive"))
      (node (ref "RN6") (pin "6") (pinfunction "1_6") (pintype "passive"))
      (node (ref "U$3") (pin "21") (pinfunction "P28_21") (pintype "bidirectional"))
      (node (ref "U$6") (pin "4") (pinfunction "G_4") (pintype "passive"))
    )
    (net (code "62") (name "Net-(RN2F-1)") (class "Default")
      (node (ref "RN2") (pin "7") (pinfunction "1_7") (pintype "passive"))
      (node (ref "RN6") (pin "7") (pinfunction "1_7") (pintype "passive"))
      (node (ref "U$3") (pin "20") (pinfunction "P27_20") (pintype "bidirectional"))
      (node (ref "U$7") (pin "2") (pinfunction "G_2") (pintype "passive"))
    )
    (net (code "63") (name "Net-(RN2G-1)") (class "Default")
      (node (ref "RN2") (pin "8") (pinfunction "1_8") (pintype "passive"))
      (node (ref "RN6") (pin "8") (pinfunction "1_8") (pintype "passive"))
      (node (ref "U$3") (pin "19") (pinfunction "P26_19") (pintype "bidirectional"))
      (node (ref "U$7") (pin "4") (pinfunction "G_4") (pintype "passive"))
    )
    (net (code "64") (name "Net-(RN3A-1)") (class "Default")
      (node (ref "RN3") (pin "2") (pinfunction "1_2") (pintype "passive"))
      (node (ref "RN5") (pin "2") (pinfunction "1_2") (pintype "passive"))
      (node (ref "U$13") (pin "2") (pinfunction "G_2") (pintype "passive"))
      (node (ref "U$3") (pin "12") (pinfunction "P19_12") (pintype "bidirectional"))
    )
    (net (code "65") (name "Net-(RN3B-1)") (class "Default")
      (node (ref "RN3") (pin "3") (pinfunction "1_3") (pintype "passive"))
      (node (ref "RN5") (pin "3") (pinfunction "1_3") (pintype "passive"))
      (node (ref "U$14") (pin "4") (pinfunction "G_4") (pintype "passive"))
      (node (ref "U$3") (pin "13") (pinfunction "P20_13") (pintype "bidirectional"))
    )
    (net (code "66") (name "Net-(RN3C-1)") (class "Default")
      (node (ref "RN3") (pin "4") (pinfunction "1_4") (pintype "passive"))
      (node (ref "RN5") (pin "4") (pinfunction "1_4") (pintype "passive"))
      (node (ref "U$14") (pin "2") (pinfunction "G_2") (pintype "passive"))
      (node (ref "U$3") (pin "14") (pinfunction "P21_14") (pintype "bidirectional"))
    )
    (net (code "67") (name "Net-(RN3D-1)") (class "Default")
      (node (ref "RN3") (pin "5") (pinfunction "1_5") (pintype "passive"))
      (node (ref "RN5") (pin "5") (pinfunction "1_5") (pintype "passive"))
      (node (ref "U$3") (pin "15") (pinfunction "P22_15") (pintype "bidirectional"))
      (node (ref "U$9") (pin "4") (pinfunction "G_4") (pintype "passive"))
    )
    (net (code "68") (name "Net-(RN3E-1)") (class "Default")
      (node (ref "RN3") (pin "6") (pinfunction "1_6") (pintype "passive"))
      (node (ref "RN5") (pin "6") (pinfunction "1_6") (pintype "passive"))
      (node (ref "U$3") (pin "16") (pinfunction "P23_16") (pintype "bidirectional"))
      (node (ref "U$9") (pin "2") (pinfunction "G_2") (pintype "passive"))
    )
    (net (code "69") (name "Net-(RN3F-1)") (class "Default")
      (node (ref "RN3") (pin "7") (pinfunction "1_7") (pintype "passive"))
      (node (ref "RN5") (pin "7") (pinfunction "1_7") (pintype "passive"))
      (node (ref "U$3") (pin "17") (pinfunction "P24_17") (pintype "bidirectional"))
      (node (ref "U$8") (pin "4") (pinfunction "G_4") (pintype "passive"))
    )
    (net (code "70") (name "Net-(RN3G-1)") (class "Default")
      (node (ref "RN3") (pin "8") (pinfunction "1_8") (pintype "passive"))
      (node (ref "RN5") (pin "8") (pinfunction "1_8") (pintype "passive"))
      (node (ref "U$3") (pin "18") (pinfunction "P25_18") (pintype "bidirectional"))
      (node (ref "U$8") (pin "2") (pinfunction "G_2") (pintype "passive"))
    )
    (net (code "71") (name "Net-(T1-B)") (class "Default")
      (node (ref "R4") (pin "1") (pinfunction "1_1") (pintype "passive"))
      (node (ref "T1") (pin "1") (pinfunction "B_1") (pintype "passive"))
      (node (ref "T2") (pin "B") (pinfunction "B_B") (pintype "passive"))
    )
    (net (code "72") (name "Net-(T1-E)") (class "Default")
      (node (ref "Q2") (pin "G") (pinfunction "G_G") (pintype "passive"))
      (node (ref "T1") (pin "2") (pinfunction "E_2") (pintype "passive"))
      (node (ref "T2") (pin "E") (pinfunction "E_E") (pintype "passive"))
    )
    (net (code "73") (name "Net-(U$2-SCL1)") (class "Default")
      (node (ref "R15") (pin "1") (pinfunction "1_1") (pintype "passive"))
      (node (ref "U$1") (pin "14") (pinfunction "14_14") (pintype "bidirectional"))
      (node (ref "U$2") (pin "3") (pinfunction "SCL1_3") (pintype "input"))
    )
    (net (code "74") (name "Net-(U$2-SCL2)") (class "Default")
      (node (ref "R12") (pin "1") (pinfunction "1_1") (pintype "passive"))
      (node (ref "U$2") (pin "6") (pinfunction "SCL2_6") (pintype "output"))
      (node (ref "U$3") (pin "26") (pinfunction "SLC_26") (pintype "input"))
    )
    (net (code "75") (name "Net-(U$2-SDA1)") (class "Default")
      (node (ref "R14") (pin "1") (pinfunction "1_1") (pintype "passive"))
      (node (ref "U$1") (pin "15") (pinfunction "15_15") (pintype "bidirectional"))
      (node (ref "U$2") (pin "2") (pinfunction "SDA1_2") (pintype "bidirectional"))
    )
    (net (code "76") (name "Net-(U$2-SDA2)") (class "Default")
      (node (ref "R11") (pin "1") (pinfunction "1_1") (pintype "passive"))
      (node (ref "U$2") (pin "7") (pinfunction "SDA2_7") (pintype "bidirectional"))
      (node (ref "U$3") (pin "25") (pinfunction "SDA_25") (pintype "bidirectional"))
    )
    (net (code "77") (name "Net-(U$3-ISET)") (class "Default")
      (node (ref "R13") (pin "2") (pinfunction "2_2") (pintype "passive"))
      (node (ref "U$3") (pin "1") (pinfunction "ISET_1") (pintype "open_collector"))
    )
    (net (code "78") (name "Net-(U$5-A)") (class "Default")
      (node (ref "R9") (pin "1") (pinfunction "1_1") (pintype "passive"))
      (node (ref "U$5") (pin "2") (pinfunction "A_2") (pintype "passive"))
    )
    (net (code "79") (name "Net-(X4C-S)") (class "Default")
      (node (ref "C18") (pin "1") (pinfunction "1_1") (pintype "passive"))
      (node (ref "U$1") (pin "8") (pinfunction "8_8") (pintype "bidirectional"))
      (node (ref "X4") (pin "3") (pinfunction "S_3") (pintype "passive"))
    )
    (net (code "80") (name "Net-(X4D-S)") (class "Default")
      (node (ref "C19") (pin "1") (pinfunction "1_1") (pintype "passive"))
      (node (ref "U$1") (pin "9") (pinfunction "9_9") (pintype "bidirectional"))
      (node (ref "X4") (pin "4") (pinfunction "S_4") (pintype "passive"))
    )
    (net (code "81") (name "Net-(X4E-S)") (class "Default")
      (node (ref "C20") (pin "1") (pinfunction "1_1") (pintype "passive"))
      (node (ref "U$1") (pin "10") (pinfunction "10_10") (pintype "bidirectional"))
      (node (ref "X4") (pin "5") (pinfunction "S_5") (pintype "passive"))
    )
    (net (code "82") (name "unconnected-(IC1A-R2OUT-Pad9)") (class "Default")
      (node (ref "IC1") (pin "9") (pinfunction "R2OUT_9") (pintype "output"))
    )
    (net (code "83") (name "unconnected-(IC1A-T2OUT-Pad7)") (class "Default")
      (node (ref "IC1") (pin "7") (pinfunction "T2OUT_7") (pintype "output"))
    )
    (net (code "84") (name "unconnected-(RN2A-1-Pad2)") (class "Default")
      (node (ref "RN2") (pin "2") (pinfunction "1_2") (pintype "passive"))
    )
    (net (code "85") (name "unconnected-(RN6A-1-Pad2)") (class "Default")
      (node (ref "RN6") (pin "2") (pinfunction "1_2") (pintype "passive"))
    )
    (net (code "86") (name "unconnected-(SERIAL-Pad1)") (class "Default")
      (node (ref "SERIAL") (pin "1") (pinfunction "1_1") (pintype "passive"))
    )
    (net (code "87") (name "unconnected-(SERIAL-Pad4)") (class "Default")
      (node (ref "SERIAL") (pin "4") (pinfunction "4_4") (pintype "passive"))
    )
    (net (code "88") (name "unconnected-(SERIAL-Pad6)") (class "Default")
      (node (ref "SERIAL") (pin "6") (pinfunction "6_6") (pintype "passive"))
    )
    (net (code "89") (name "unconnected-(SERIAL-Pad7)") (class "Default")
      (node (ref "SERIAL") (pin "7") (pinfunction "7_7") (pintype "passive"))
    )
    (net (code "90") (name "unconnected-(SERIAL-Pad8)") (class "Default")
      (node (ref "SERIAL") (pin "8") (pinfunction "8_8") (pintype "passive"))
    )
    (net (code "91") (name "unconnected-(SERIAL-Pad9)") (class "Default")
      (node (ref "SERIAL") (pin "9") (pinfunction "9_9") (pintype "passive"))
    )
    (net (code "92") (name "unconnected-(U$1-Pad2)") (class "Default")
      (node (ref "U$1") (pin "2") (pinfunction "2_2") (pintype "bidirectional"))
    )
    (net (code "93") (name "unconnected-(U$1-Pad5)") (class "Default")
      (node (ref "U$1") (pin "5") (pinfunction "5_5") (pintype "bidirectional"))
    )
    (net (code "94") (name "unconnected-(U$1-Pad6)") (class "Default")
      (node (ref "U$1") (pin "6") (pinfunction "6_6") (pintype "bidirectional"))
    )
    (net (code "95") (name "unconnected-(U$1-Pad11)") (class "Default")
      (node (ref "U$1") (pin "11") (pinfunction "11_11") (pintype "bidirectional"))
    )
    (net (code "96") (name "unconnected-(U$1-Pad12)") (class "Default")
      (node (ref "U$1") (pin "12") (pinfunction "12_12") (pintype "bidirectional"))
    )
    (net (code "97") (name "unconnected-(U$1-Pad13)") (class "Default")
      (node (ref "U$1") (pin "13") (pinfunction "13_13") (pintype "bidirectional"))
    )
    (net (code "98") (name "unconnected-(U$1-Pad18)") (class "Default")
      (node (ref "U$1") (pin "18") (pinfunction "18_18") (pintype "bidirectional"))
    )
    (net (code "99") (name "unconnected-(U$1-Pad19)") (class "Default")
      (node (ref "U$1") (pin "19") (pinfunction "19_19") (pintype "bidirectional"))
    )
  )
)
